# relays0.net
KiCad netlist of a schematic drawn in Altium Designer
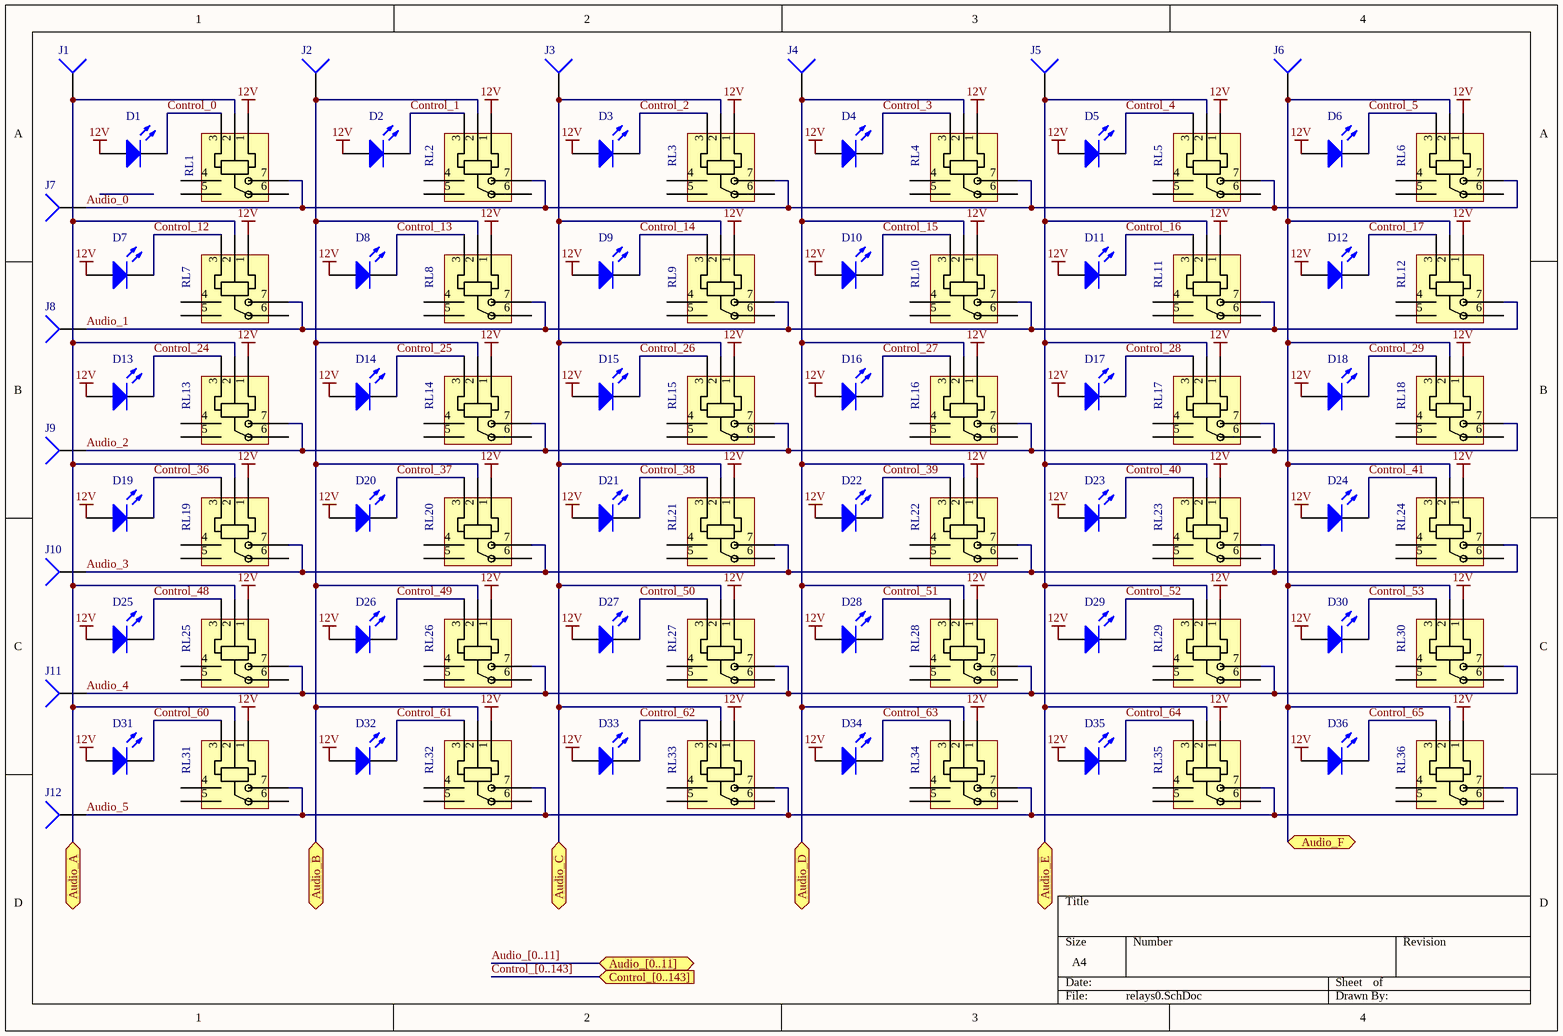
[diagram p0: relays0.SchDoc]

(export (version "E")
  (design (tool "Eeschema 10.0.6"))
  (components
    (comp (ref "D1")
      (value "LED0")
      (footprint "LED_round_5mm")
      (description "Typical INFRARED GaAs LED")
      (fields (field (name "PUBLISHER") "Altium Limited"))
      (libsource (lib "Miscellaneous Devices") (part "LED0"))
    )
    (comp (ref "D2")
      (value "LED0")
      (footprint "LED_round_5mm")
      (description "Typical INFRARED GaAs LED")
      (fields (field (name "PUBLISHER") "Altium Limited"))
      (libsource (lib "Miscellaneous Devices") (part "LED0"))
    )
    (comp (ref "D3")
      (value "LED0")
      (footprint "LED_round_5mm")
      (description "Typical INFRARED GaAs LED")
      (fields (field (name "PUBLISHER") "Altium Limited"))
      (libsource (lib "Miscellaneous Devices") (part "LED0"))
    )
    (comp (ref "D4")
      (value "LED0")
      (footprint "LED_round_5mm")
      (description "Typical INFRARED GaAs LED")
      (fields (field (name "PUBLISHER") "Altium Limited"))
      (libsource (lib "Miscellaneous Devices") (part "LED0"))
    )
    (comp (ref "D5")
      (value "LED0")
      (footprint "LED_round_5mm")
      (description "Typical INFRARED GaAs LED")
      (fields (field (name "PUBLISHER") "Altium Limited"))
      (libsource (lib "Miscellaneous Devices") (part "LED0"))
    )
    (comp (ref "D6")
      (value "LED0")
      (footprint "LED_round_5mm")
      (description "Typical INFRARED GaAs LED")
      (fields (field (name "PUBLISHER") "Altium Limited"))
      (libsource (lib "Miscellaneous Devices") (part "LED0"))
    )
    (comp (ref "D7")
      (value "LED0")
      (footprint "LED_round_5mm")
      (description "Typical INFRARED GaAs LED")
      (fields (field (name "PUBLISHER") "Altium Limited"))
      (libsource (lib "Miscellaneous Devices") (part "LED0"))
    )
    (comp (ref "D8")
      (value "LED0")
      (footprint "LED_round_5mm")
      (description "Typical INFRARED GaAs LED")
      (fields (field (name "PUBLISHER") "Altium Limited"))
      (libsource (lib "Miscellaneous Devices") (part "LED0"))
    )
    (comp (ref "D9")
      (value "LED0")
      (footprint "LED_round_5mm")
      (description "Typical INFRARED GaAs LED")
      (fields (field (name "PUBLISHER") "Altium Limited"))
      (libsource (lib "Miscellaneous Devices") (part "LED0"))
    )
    (comp (ref "D10")
      (value "LED0")
      (footprint "LED_round_5mm")
      (description "Typical INFRARED GaAs LED")
      (fields (field (name "PUBLISHER") "Altium Limited"))
      (libsource (lib "Miscellaneous Devices") (part "LED0"))
    )
    (comp (ref "D11")
      (value "LED0")
      (footprint "LED_round_5mm")
      (description "Typical INFRARED GaAs LED")
      (fields (field (name "PUBLISHER") "Altium Limited"))
      (libsource (lib "Miscellaneous Devices") (part "LED0"))
    )
    (comp (ref "D12")
      (value "LED0")
      (footprint "LED_round_5mm")
      (description "Typical INFRARED GaAs LED")
      (fields (field (name "PUBLISHER") "Altium Limited"))
      (libsource (lib "Miscellaneous Devices") (part "LED0"))
    )
    (comp (ref "D13")
      (value "LED0")
      (footprint "LED_round_5mm")
      (description "Typical INFRARED GaAs LED")
      (fields (field (name "PUBLISHER") "Altium Limited"))
      (libsource (lib "Miscellaneous Devices") (part "LED0"))
    )
    (comp (ref "D14")
      (value "LED0")
      (footprint "LED_round_5mm")
      (description "Typical INFRARED GaAs LED")
      (fields (field (name "PUBLISHER") "Altium Limited"))
      (libsource (lib "Miscellaneous Devices") (part "LED0"))
    )
    (comp (ref "D15")
      (value "LED0")
      (footprint "LED_round_5mm")
      (description "Typical INFRARED GaAs LED")
      (fields (field (name "PUBLISHER") "Altium Limited"))
      (libsource (lib "Miscellaneous Devices") (part "LED0"))
    )
    (comp (ref "D16")
      (value "LED0")
      (footprint "LED_round_5mm")
      (description "Typical INFRARED GaAs LED")
      (fields (field (name "PUBLISHER") "Altium Limited"))
      (libsource (lib "Miscellaneous Devices") (part "LED0"))
    )
    (comp (ref "D17")
      (value "LED0")
      (footprint "LED_round_5mm")
      (description "Typical INFRARED GaAs LED")
      (fields (field (name "PUBLISHER") "Altium Limited"))
      (libsource (lib "Miscellaneous Devices") (part "LED0"))
    )
    (comp (ref "D18")
      (value "LED0")
      (footprint "LED_round_5mm")
      (description "Typical INFRARED GaAs LED")
      (fields (field (name "PUBLISHER") "Altium Limited"))
      (libsource (lib "Miscellaneous Devices") (part "LED0"))
    )
    (comp (ref "D19")
      (value "LED0")
      (footprint "LED_round_5mm")
      (description "Typical INFRARED GaAs LED")
      (fields (field (name "PUBLISHER") "Altium Limited"))
      (libsource (lib "Miscellaneous Devices") (part "LED0"))
    )
    (comp (ref "D20")
      (value "LED0")
      (footprint "LED_round_5mm")
      (description "Typical INFRARED GaAs LED")
      (fields (field (name "PUBLISHER") "Altium Limited"))
      (libsource (lib "Miscellaneous Devices") (part "LED0"))
    )
    (comp (ref "D21")
      (value "LED0")
      (footprint "LED_round_5mm")
      (description "Typical INFRARED GaAs LED")
      (fields (field (name "PUBLISHER") "Altium Limited"))
      (libsource (lib "Miscellaneous Devices") (part "LED0"))
    )
    (comp (ref "D22")
      (value "LED0")
      (footprint "LED_round_5mm")
      (description "Typical INFRARED GaAs LED")
      (fields (field (name "PUBLISHER") "Altium Limited"))
      (libsource (lib "Miscellaneous Devices") (part "LED0"))
    )
    (comp (ref "D23")
      (value "LED0")
      (footprint "LED_round_5mm")
      (description "Typical INFRARED GaAs LED")
      (fields (field (name "PUBLISHER") "Altium Limited"))
      (libsource (lib "Miscellaneous Devices") (part "LED0"))
    )
    (comp (ref "D24")
      (value "LED0")
      (footprint "LED_round_5mm")
      (description "Typical INFRARED GaAs LED")
      (fields (field (name "PUBLISHER") "Altium Limited"))
      (libsource (lib "Miscellaneous Devices") (part "LED0"))
    )
    (comp (ref "D25")
      (value "LED0")
      (footprint "LED_round_5mm")
      (description "Typical INFRARED GaAs LED")
      (fields (field (name "PUBLISHER") "Altium Limited"))
      (libsource (lib "Miscellaneous Devices") (part "LED0"))
    )
    (comp (ref "D26")
      (value "LED0")
      (footprint "LED_round_5mm")
      (description "Typical INFRARED GaAs LED")
      (fields (field (name "PUBLISHER") "Altium Limited"))
      (libsource (lib "Miscellaneous Devices") (part "LED0"))
    )
    (comp (ref "D27")
      (value "LED0")
      (footprint "LED_round_5mm")
      (description "Typical INFRARED GaAs LED")
      (fields (field (name "PUBLISHER") "Altium Limited"))
      (libsource (lib "Miscellaneous Devices") (part "LED0"))
    )
    (comp (ref "D28")
      (value "LED0")
      (footprint "LED_round_5mm")
      (description "Typical INFRARED GaAs LED")
      (fields (field (name "PUBLISHER") "Altium Limited"))
      (libsource (lib "Miscellaneous Devices") (part "LED0"))
    )
    (comp (ref "D29")
      (value "LED0")
      (footprint "LED_round_5mm")
      (description "Typical INFRARED GaAs LED")
      (fields (field (name "PUBLISHER") "Altium Limited"))
      (libsource (lib "Miscellaneous Devices") (part "LED0"))
    )
    (comp (ref "D30")
      (value "LED0")
      (footprint "LED_round_5mm")
      (description "Typical INFRARED GaAs LED")
      (fields (field (name "PUBLISHER") "Altium Limited"))
      (libsource (lib "Miscellaneous Devices") (part "LED0"))
    )
    (comp (ref "D31")
      (value "LED0")
      (footprint "LED_round_5mm")
      (description "Typical INFRARED GaAs LED")
      (fields (field (name "PUBLISHER") "Altium Limited"))
      (libsource (lib "Miscellaneous Devices") (part "LED0"))
    )
    (comp (ref "D32")
      (value "LED0")
      (footprint "LED_round_5mm")
      (description "Typical INFRARED GaAs LED")
      (fields (field (name "PUBLISHER") "Altium Limited"))
      (libsource (lib "Miscellaneous Devices") (part "LED0"))
    )
    (comp (ref "D33")
      (value "LED0")
      (footprint "LED_round_5mm")
      (description "Typical INFRARED GaAs LED")
      (fields (field (name "PUBLISHER") "Altium Limited"))
      (libsource (lib "Miscellaneous Devices") (part "LED0"))
    )
    (comp (ref "D34")
      (value "LED0")
      (footprint "LED_round_5mm")
      (description "Typical INFRARED GaAs LED")
      (fields (field (name "PUBLISHER") "Altium Limited"))
      (libsource (lib "Miscellaneous Devices") (part "LED0"))
    )
    (comp (ref "D35")
      (value "LED0")
      (footprint "LED_round_5mm")
      (description "Typical INFRARED GaAs LED")
      (fields (field (name "PUBLISHER") "Altium Limited"))
      (libsource (lib "Miscellaneous Devices") (part "LED0"))
    )
    (comp (ref "D36")
      (value "LED0")
      (footprint "LED_round_5mm")
      (description "Typical INFRARED GaAs LED")
      (fields (field (name "PUBLISHER") "Altium Limited"))
      (libsource (lib "Miscellaneous Devices") (part "LED0"))
    )
    (comp (ref "J1")
      (value "Audio")
      (footprint "Conn_1_2x4")
      (description "Socket")
      (fields (field (name "PUBLISHER") "Altium Limited"))
      (libsource (lib "Miscellaneous Connectors") (part "Socket"))
    )
    (comp (ref "J2")
      (value "Audio")
      (footprint "Conn_1_2x4")
      (description "Socket")
      (fields (field (name "PUBLISHER") "Altium Limited"))
      (libsource (lib "Miscellaneous Connectors") (part "Socket"))
    )
    (comp (ref "J3")
      (value "Audio")
      (footprint "Conn_1_2x4")
      (description "Socket")
      (fields (field (name "PUBLISHER") "Altium Limited"))
      (libsource (lib "Miscellaneous Connectors") (part "Socket"))
    )
    (comp (ref "J4")
      (value "Audio")
      (footprint "Conn_1_2x4")
      (description "Socket")
      (fields (field (name "PUBLISHER") "Altium Limited"))
      (libsource (lib "Miscellaneous Connectors") (part "Socket"))
    )
    (comp (ref "J5")
      (value "Audio")
      (footprint "Conn_1_2x4")
      (description "Socket")
      (fields (field (name "PUBLISHER") "Altium Limited"))
      (libsource (lib "Miscellaneous Connectors") (part "Socket"))
    )
    (comp (ref "J6")
      (value "Audio")
      (footprint "Conn_1_2x4")
      (description "Socket")
      (fields (field (name "PUBLISHER") "Altium Limited"))
      (libsource (lib "Miscellaneous Connectors") (part "Socket"))
    )
    (comp (ref "J7")
      (value "Audio")
      (footprint "Conn_1_2x4")
      (description "Socket")
      (fields (field (name "PUBLISHER") "Altium Limited"))
      (libsource (lib "Miscellaneous Connectors") (part "Socket"))
    )
    (comp (ref "J8")
      (value "Audio")
      (footprint "Conn_1_2x4")
      (description "Socket")
      (fields (field (name "PUBLISHER") "Altium Limited"))
      (libsource (lib "Miscellaneous Connectors") (part "Socket"))
    )
    (comp (ref "J9")
      (value "Audio")
      (footprint "Conn_1_2x4")
      (description "Socket")
      (fields (field (name "PUBLISHER") "Altium Limited"))
      (libsource (lib "Miscellaneous Connectors") (part "Socket"))
    )
    (comp (ref "J10")
      (value "Audio")
      (footprint "Conn_1_2x4")
      (description "Socket")
      (fields (field (name "PUBLISHER") "Altium Limited"))
      (libsource (lib "Miscellaneous Connectors") (part "Socket"))
    )
    (comp (ref "J11")
      (value "Audio")
      (footprint "Conn_1_2x4")
      (description "Socket")
      (fields (field (name "PUBLISHER") "Altium Limited"))
      (libsource (lib "Miscellaneous Connectors") (part "Socket"))
    )
    (comp (ref "J12")
      (value "Audio")
      (footprint "Conn_1_2x4")
      (description "Socket")
      (fields (field (name "PUBLISHER") "Altium Limited"))
      (libsource (lib "Miscellaneous Connectors") (part "Socket"))
    )
    (comp (ref "RL1")
      (value "Relay")
      (footprint "Relay_FRA3")
      (description "Miniature power relay")
      (fields (field (name "PART NUMBER") "FRA3C-DC12"))
      (libsource (lib "tech-thing") (part "Relay_FRA3"))
    )
    (comp (ref "RL2")
      (value "Relay")
      (footprint "Relay_FRA3")
      (description "Miniature power relay")
      (fields (field (name "PART NUMBER") "FRA3C-DC12"))
      (libsource (lib "tech-thing") (part "Relay_FRA3"))
    )
    (comp (ref "RL3")
      (value "Relay")
      (footprint "Relay_FRA3")
      (description "Miniature power relay")
      (fields (field (name "PART NUMBER") "FRA3C-DC12"))
      (libsource (lib "tech-thing") (part "Relay_FRA3"))
    )
    (comp (ref "RL4")
      (value "Relay")
      (footprint "Relay_FRA3")
      (description "Miniature power relay")
      (fields (field (name "PART NUMBER") "FRA3C-DC12"))
      (libsource (lib "tech-thing") (part "Relay_FRA3"))
    )
    (comp (ref "RL5")
      (value "Relay")
      (footprint "Relay_FRA3")
      (description "Miniature power relay")
      (fields (field (name "PART NUMBER") "FRA3C-DC12"))
      (libsource (lib "tech-thing") (part "Relay_FRA3"))
    )
    (comp (ref "RL6")
      (value "Relay")
      (footprint "Relay_FRA3")
      (description "Miniature power relay")
      (fields (field (name "PART NUMBER") "FRA3C-DC12"))
      (libsource (lib "tech-thing") (part "Relay_FRA3"))
    )
    (comp (ref "RL7")
      (value "Relay")
      (footprint "Relay_FRA3")
      (description "Miniature power relay")
      (fields (field (name "PART NUMBER") "FRA3C-DC12"))
      (libsource (lib "tech-thing") (part "Relay_FRA3"))
    )
    (comp (ref "RL8")
      (value "Relay")
      (footprint "Relay_FRA3")
      (description "Miniature power relay")
      (fields (field (name "PART NUMBER") "FRA3C-DC12"))
      (libsource (lib "tech-thing") (part "Relay_FRA3"))
    )
    (comp (ref "RL9")
      (value "Relay")
      (footprint "Relay_FRA3")
      (description "Miniature power relay")
      (fields (field (name "PART NUMBER") "FRA3C-DC12"))
      (libsource (lib "tech-thing") (part "Relay_FRA3"))
    )
    (comp (ref "RL10")
      (value "Relay")
      (footprint "Relay_FRA3")
      (description "Miniature power relay")
      (fields (field (name "PART NUMBER") "FRA3C-DC12"))
      (libsource (lib "tech-thing") (part "Relay_FRA3"))
    )
    (comp (ref "RL11")
      (value "Relay")
      (footprint "Relay_FRA3")
      (description "Miniature power relay")
      (fields (field (name "PART NUMBER") "FRA3C-DC12"))
      (libsource (lib "tech-thing") (part "Relay_FRA3"))
    )
    (comp (ref "RL12")
      (value "Relay")
      (footprint "Relay_FRA3")
      (description "Miniature power relay")
      (fields (field (name "PART NUMBER") "FRA3C-DC12"))
      (libsource (lib "tech-thing") (part "Relay_FRA3"))
    )
    (comp (ref "RL13")
      (value "Relay")
      (footprint "Relay_FRA3")
      (description "Miniature power relay")
      (fields (field (name "PART NUMBER") "FRA3C-DC12"))
      (libsource (lib "tech-thing") (part "Relay_FRA3"))
    )
    (comp (ref "RL14")
      (value "Relay")
      (footprint "Relay_FRA3")
      (description "Miniature power relay")
      (fields (field (name "PART NUMBER") "FRA3C-DC12"))
      (libsource (lib "tech-thing") (part "Relay_FRA3"))
    )
    (comp (ref "RL15")
      (value "Relay")
      (footprint "Relay_FRA3")
      (description "Miniature power relay")
      (fields (field (name "PART NUMBER") "FRA3C-DC12"))
      (libsource (lib "tech-thing") (part "Relay_FRA3"))
    )
    (comp (ref "RL16")
      (value "Relay")
      (footprint "Relay_FRA3")
      (description "Miniature power relay")
      (fields (field (name "PART NUMBER") "FRA3C-DC12"))
      (libsource (lib "tech-thing") (part "Relay_FRA3"))
    )
    (comp (ref "RL17")
      (value "Relay")
      (footprint "Relay_FRA3")
      (description "Miniature power relay")
      (fields (field (name "PART NUMBER") "FRA3C-DC12"))
      (libsource (lib "tech-thing") (part "Relay_FRA3"))
    )
    (comp (ref "RL18")
      (value "Relay")
      (footprint "Relay_FRA3")
      (description "Miniature power relay")
      (fields (field (name "PART NUMBER") "FRA3C-DC12"))
      (libsource (lib "tech-thing") (part "Relay_FRA3"))
    )
    (comp (ref "RL19")
      (value "Relay")
      (footprint "Relay_FRA3")
      (description "Miniature power relay")
      (fields (field (name "PART NUMBER") "FRA3C-DC12"))
      (libsource (lib "tech-thing") (part "Relay_FRA3"))
    )
    (comp (ref "RL20")
      (value "Relay")
      (footprint "Relay_FRA3")
      (description "Miniature power relay")
      (fields (field (name "PART NUMBER") "FRA3C-DC12"))
      (libsource (lib "tech-thing") (part "Relay_FRA3"))
    )
    (comp (ref "RL21")
      (value "Relay")
      (footprint "Relay_FRA3")
      (description "Miniature power relay")
      (fields (field (name "PART NUMBER") "FRA3C-DC12"))
      (libsource (lib "tech-thing") (part "Relay_FRA3"))
    )
    (comp (ref "RL22")
      (value "Relay")
      (footprint "Relay_FRA3")
      (description "Miniature power relay")
      (fields (field (name "PART NUMBER") "FRA3C-DC12"))
      (libsource (lib "tech-thing") (part "Relay_FRA3"))
    )
    (comp (ref "RL23")
      (value "Relay")
      (footprint "Relay_FRA3")
      (description "Miniature power relay")
      (fields (field (name "PART NUMBER") "FRA3C-DC12"))
      (libsource (lib "tech-thing") (part "Relay_FRA3"))
    )
    (comp (ref "RL24")
      (value "Relay")
      (footprint "Relay_FRA3")
      (description "Miniature power relay")
      (fields (field (name "PART NUMBER") "FRA3C-DC12"))
      (libsource (lib "tech-thing") (part "Relay_FRA3"))
    )
    (comp (ref "RL25")
      (value "Relay")
      (footprint "Relay_FRA3")
      (description "Miniature power relay")
      (fields (field (name "PART NUMBER") "FRA3C-DC12"))
      (libsource (lib "tech-thing") (part "Relay_FRA3"))
    )
    (comp (ref "RL26")
      (value "Relay")
      (footprint "Relay_FRA3")
      (description "Miniature power relay")
      (fields (field (name "PART NUMBER") "FRA3C-DC12"))
      (libsource (lib "tech-thing") (part "Relay_FRA3"))
    )
    (comp (ref "RL27")
      (value "Relay")
      (footprint "Relay_FRA3")
      (description "Miniature power relay")
      (fields (field (name "PART NUMBER") "FRA3C-DC12"))
      (libsource (lib "tech-thing") (part "Relay_FRA3"))
    )
    (comp (ref "RL28")
      (value "Relay")
      (footprint "Relay_FRA3")
      (description "Miniature power relay")
      (fields (field (name "PART NUMBER") "FRA3C-DC12"))
      (libsource (lib "tech-thing") (part "Relay_FRA3"))
    )
    (comp (ref "RL29")
      (value "Relay")
      (footprint "Relay_FRA3")
      (description "Miniature power relay")
      (fields (field (name "PART NUMBER") "FRA3C-DC12"))
      (libsource (lib "tech-thing") (part "Relay_FRA3"))
    )
    (comp (ref "RL30")
      (value "Relay")
      (footprint "Relay_FRA3")
      (description "Miniature power relay")
      (fields (field (name "PART NUMBER") "FRA3C-DC12"))
      (libsource (lib "tech-thing") (part "Relay_FRA3"))
    )
    (comp (ref "RL31")
      (value "Relay")
      (footprint "Relay_FRA3")
      (description "Miniature power relay")
      (fields (field (name "PART NUMBER") "FRA3C-DC12"))
      (libsource (lib "tech-thing") (part "Relay_FRA3"))
    )
    (comp (ref "RL32")
      (value "Relay")
      (footprint "Relay_FRA3")
      (description "Miniature power relay")
      (fields (field (name "PART NUMBER") "FRA3C-DC12"))
      (libsource (lib "tech-thing") (part "Relay_FRA3"))
    )
    (comp (ref "RL33")
      (value "Relay")
      (footprint "Relay_FRA3")
      (description "Miniature power relay")
      (fields (field (name "PART NUMBER") "FRA3C-DC12"))
      (libsource (lib "tech-thing") (part "Relay_FRA3"))
    )
    (comp (ref "RL34")
      (value "Relay")
      (footprint "Relay_FRA3")
      (description "Miniature power relay")
      (fields (field (name "PART NUMBER") "FRA3C-DC12"))
      (libsource (lib "tech-thing") (part "Relay_FRA3"))
    )
    (comp (ref "RL35")
      (value "Relay")
      (footprint "Relay_FRA3")
      (description "Miniature power relay")
      (fields (field (name "PART NUMBER") "FRA3C-DC12"))
      (libsource (lib "tech-thing") (part "Relay_FRA3"))
    )
    (comp (ref "RL36")
      (value "Relay")
      (footprint "Relay_FRA3")
      (description "Miniature power relay")
      (fields (field (name "PART NUMBER") "FRA3C-DC12"))
      (libsource (lib "tech-thing") (part "Relay_FRA3"))
    )
  )
  (nets
    (net (code "115") (name "/Audio_0") (class "Default")
      (node (ref "J7") (pin "1") (pinfunction "1_1") (pintype "passive"))
      (node (ref "RL1") (pin "7") (pintype "passive"))
      (node (ref "RL2") (pin "7") (pintype "passive"))
      (node (ref "RL3") (pin "7") (pintype "passive"))
      (node (ref "RL4") (pin "7") (pintype "passive"))
      (node (ref "RL5") (pin "7") (pintype "passive"))
      (node (ref "RL6") (pin "7") (pintype "passive"))
    )
    (net (code "116") (name "/Audio_1") (class "Default")
      (node (ref "J8") (pin "1") (pinfunction "1_1") (pintype "passive"))
      (node (ref "RL10") (pin "7") (pintype "passive"))
      (node (ref "RL11") (pin "7") (pintype "passive"))
      (node (ref "RL12") (pin "7") (pintype "passive"))
      (node (ref "RL7") (pin "7") (pintype "passive"))
      (node (ref "RL8") (pin "7") (pintype "passive"))
      (node (ref "RL9") (pin "7") (pintype "passive"))
    )
    (net (code "117") (name "/Audio_2") (class "Default")
      (node (ref "J9") (pin "1") (pinfunction "1_1") (pintype "passive"))
      (node (ref "RL13") (pin "7") (pintype "passive"))
      (node (ref "RL14") (pin "7") (pintype "passive"))
      (node (ref "RL15") (pin "7") (pintype "passive"))
      (node (ref "RL16") (pin "7") (pintype "passive"))
      (node (ref "RL17") (pin "7") (pintype "passive"))
      (node (ref "RL18") (pin "7") (pintype "passive"))
    )
    (net (code "118") (name "/Audio_3") (class "Default")
      (node (ref "J10") (pin "1") (pinfunction "1_1") (pintype "passive"))
      (node (ref "RL19") (pin "7") (pintype "passive"))
      (node (ref "RL20") (pin "7") (pintype "passive"))
      (node (ref "RL21") (pin "7") (pintype "passive"))
      (node (ref "RL22") (pin "7") (pintype "passive"))
      (node (ref "RL23") (pin "7") (pintype "passive"))
      (node (ref "RL24") (pin "7") (pintype "passive"))
    )
    (net (code "119") (name "/Audio_4") (class "Default")
      (node (ref "J11") (pin "1") (pinfunction "1_1") (pintype "passive"))
      (node (ref "RL25") (pin "7") (pintype "passive"))
      (node (ref "RL26") (pin "7") (pintype "passive"))
      (node (ref "RL27") (pin "7") (pintype "passive"))
      (node (ref "RL28") (pin "7") (pintype "passive"))
      (node (ref "RL29") (pin "7") (pintype "passive"))
      (node (ref "RL30") (pin "7") (pintype "passive"))
    )
    (net (code "120") (name "/Audio_5") (class "Default")
      (node (ref "J12") (pin "1") (pinfunction "1_1") (pintype "passive"))
      (node (ref "RL31") (pin "7") (pintype "passive"))
      (node (ref "RL32") (pin "7") (pintype "passive"))
      (node (ref "RL33") (pin "7") (pintype "passive"))
      (node (ref "RL34") (pin "7") (pintype "passive"))
      (node (ref "RL35") (pin "7") (pintype "passive"))
      (node (ref "RL36") (pin "7") (pintype "passive"))
    )
    (net (code "121") (name "/Audio_A") (class "Default")
      (node (ref "J1") (pin "1") (pinfunction "1_1") (pintype "passive"))
      (node (ref "RL1") (pin "2") (pintype "passive"))
      (node (ref "RL13") (pin "2") (pintype "passive"))
      (node (ref "RL19") (pin "2") (pintype "passive"))
      (node (ref "RL25") (pin "2") (pintype "passive"))
      (node (ref "RL31") (pin "2") (pintype "passive"))
      (node (ref "RL7") (pin "2") (pintype "passive"))
    )
    (net (code "122") (name "/Audio_B") (class "Default")
      (node (ref "J2") (pin "1") (pinfunction "1_1") (pintype "passive"))
      (node (ref "RL14") (pin "2") (pintype "passive"))
      (node (ref "RL2") (pin "2") (pintype "passive"))
      (node (ref "RL20") (pin "2") (pintype "passive"))
      (node (ref "RL26") (pin "2") (pintype "passive"))
      (node (ref "RL32") (pin "2") (pintype "passive"))
      (node (ref "RL8") (pin "2") (pintype "passive"))
    )
    (net (code "123") (name "/Audio_C") (class "Default")
      (node (ref "J3") (pin "1") (pinfunction "1_1") (pintype "passive"))
      (node (ref "RL15") (pin "2") (pintype "passive"))
      (node (ref "RL21") (pin "2") (pintype "passive"))
      (node (ref "RL27") (pin "2") (pintype "passive"))
      (node (ref "RL3") (pin "2") (pintype "passive"))
      (node (ref "RL33") (pin "2") (pintype "passive"))
      (node (ref "RL9") (pin "2") (pintype "passive"))
    )
    (net (code "124") (name "/Audio_D") (class "Default")
      (node (ref "J4") (pin "1") (pinfunction "1_1") (pintype "passive"))
      (node (ref "RL10") (pin "2") (pintype "passive"))
      (node (ref "RL16") (pin "2") (pintype "passive"))
      (node (ref "RL22") (pin "2") (pintype "passive"))
      (node (ref "RL28") (pin "2") (pintype "passive"))
      (node (ref "RL34") (pin "2") (pintype "passive"))
      (node (ref "RL4") (pin "2") (pintype "passive"))
    )
    (net (code "125") (name "/Audio_E") (class "Default")
      (node (ref "J5") (pin "1") (pinfunction "1_1") (pintype "passive"))
      (node (ref "RL11") (pin "2") (pintype "passive"))
      (node (ref "RL17") (pin "2") (pintype "passive"))
      (node (ref "RL23") (pin "2") (pintype "passive"))
      (node (ref "RL29") (pin "2") (pintype "passive"))
      (node (ref "RL35") (pin "2") (pintype "passive"))
      (node (ref "RL5") (pin "2") (pintype "passive"))
    )
    (net (code "126") (name "/Audio_F") (class "Default")
      (node (ref "J6") (pin "1") (pinfunction "1_1") (pintype "passive"))
      (node (ref "RL12") (pin "2") (pintype "passive"))
      (node (ref "RL18") (pin "2") (pintype "passive"))
      (node (ref "RL24") (pin "2") (pintype "passive"))
      (node (ref "RL30") (pin "2") (pintype "passive"))
      (node (ref "RL36") (pin "2") (pintype "passive"))
      (node (ref "RL6") (pin "2") (pintype "passive"))
    )
    (net (code "128") (name "/Control_0") (class "Default")
      (node (ref "D1") (pin "2") (pinfunction "K_2") (pintype "passive"))
      (node (ref "RL1") (pin "3") (pintype "passive"))
    )
    (net (code "129") (name "/Control_1") (class "Default")
      (node (ref "D2") (pin "2") (pinfunction "K_2") (pintype "passive"))
      (node (ref "RL2") (pin "3") (pintype "passive"))
    )
    (net (code "130") (name "/Control_2") (class "Default")
      (node (ref "D3") (pin "2") (pinfunction "K_2") (pintype "passive"))
      (node (ref "RL3") (pin "3") (pintype "passive"))
    )
    (net (code "131") (name "/Control_3") (class "Default")
      (node (ref "D4") (pin "2") (pinfunction "K_2") (pintype "passive"))
      (node (ref "RL4") (pin "3") (pintype "passive"))
    )
    (net (code "132") (name "/Control_4") (class "Default")
      (node (ref "D5") (pin "2") (pinfunction "K_2") (pintype "passive"))
      (node (ref "RL5") (pin "3") (pintype "passive"))
    )
    (net (code "133") (name "/Control_5") (class "Default")
      (node (ref "D6") (pin "2") (pinfunction "K_2") (pintype "passive"))
      (node (ref "RL6") (pin "3") (pintype "passive"))
    )
    (net (code "134") (name "/Control_12") (class "Default")
      (node (ref "D7") (pin "2") (pinfunction "K_2") (pintype "passive"))
      (node (ref "RL7") (pin "3") (pintype "passive"))
    )
    (net (code "135") (name "/Control_13") (class "Default")
      (node (ref "D8") (pin "2") (pinfunction "K_2") (pintype "passive"))
      (node (ref "RL8") (pin "3") (pintype "passive"))
    )
    (net (code "136") (name "/Control_14") (class "Default")
      (node (ref "D9") (pin "2") (pinfunction "K_2") (pintype "passive"))
      (node (ref "RL9") (pin "3") (pintype "passive"))
    )
    (net (code "137") (name "/Control_15") (class "Default")
      (node (ref "D10") (pin "2") (pinfunction "K_2") (pintype "passive"))
      (node (ref "RL10") (pin "3") (pintype "passive"))
    )
    (net (code "138") (name "/Control_16") (class "Default")
      (node (ref "D11") (pin "2") (pinfunction "K_2") (pintype "passive"))
      (node (ref "RL11") (pin "3") (pintype "passive"))
    )
    (net (code "139") (name "/Control_17") (class "Default")
      (node (ref "D12") (pin "2") (pinfunction "K_2") (pintype "passive"))
      (node (ref "RL12") (pin "3") (pintype "passive"))
    )
    (net (code "140") (name "/Control_24") (class "Default")
      (node (ref "D13") (pin "2") (pinfunction "K_2") (pintype "passive"))
      (node (ref "RL13") (pin "3") (pintype "passive"))
    )
    (net (code "141") (name "/Control_25") (class "Default")
      (node (ref "D14") (pin "2") (pinfunction "K_2") (pintype "passive"))
      (node (ref "RL14") (pin "3") (pintype "passive"))
    )
    (net (code "142") (name "/Control_26") (class "Default")
      (node (ref "D15") (pin "2") (pinfunction "K_2") (pintype "passive"))
      (node (ref "RL15") (pin "3") (pintype "passive"))
    )
    (net (code "143") (name "/Control_27") (class "Default")
      (node (ref "D16") (pin "2") (pinfunction "K_2") (pintype "passive"))
      (node (ref "RL16") (pin "3") (pintype "passive"))
    )
    (net (code "144") (name "/Control_28") (class "Default")
      (node (ref "D17") (pin "2") (pinfunction "K_2") (pintype "passive"))
      (node (ref "RL17") (pin "3") (pintype "passive"))
    )
    (net (code "145") (name "/Control_29") (class "Default")
      (node (ref "D18") (pin "2") (pinfunction "K_2") (pintype "passive"))
      (node (ref "RL18") (pin "3") (pintype "passive"))
    )
    (net (code "146") (name "/Control_36") (class "Default")
      (node (ref "D19") (pin "2") (pinfunction "K_2") (pintype "passive"))
      (node (ref "RL19") (pin "3") (pintype "passive"))
    )
    (net (code "147") (name "/Control_37") (class "Default")
      (node (ref "D20") (pin "2") (pinfunction "K_2") (pintype "passive"))
      (node (ref "RL20") (pin "3") (pintype "passive"))
    )
    (net (code "148") (name "/Control_38") (class "Default")
      (node (ref "D21") (pin "2") (pinfunction "K_2") (pintype "passive"))
      (node (ref "RL21") (pin "3") (pintype "passive"))
    )
    (net (code "149") (name "/Control_39") (class "Default")
      (node (ref "D22") (pin "2") (pinfunction "K_2") (pintype "passive"))
      (node (ref "RL22") (pin "3") (pintype "passive"))
    )
    (net (code "150") (name "/Control_40") (class "Default")
      (node (ref "D23") (pin "2") (pinfunction "K_2") (pintype "passive"))
      (node (ref "RL23") (pin "3") (pintype "passive"))
    )
    (net (code "151") (name "/Control_41") (class "Default")
      (node (ref "D24") (pin "2") (pinfunction "K_2") (pintype "passive"))
      (node (ref "RL24") (pin "3") (pintype "passive"))
    )
    (net (code "152") (name "/Control_48") (class "Default")
      (node (ref "D25") (pin "2") (pinfunction "K_2") (pintype "passive"))
      (node (ref "RL25") (pin "3") (pintype "passive"))
    )
    (net (code "153") (name "/Control_49") (class "Default")
      (node (ref "D26") (pin "2") (pinfunction "K_2") (pintype "passive"))
      (node (ref "RL26") (pin "3") (pintype "passive"))
    )
    (net (code "154") (name "/Control_50") (class "Default")
      (node (ref "D27") (pin "2") (pinfunction "K_2") (pintype "passive"))
      (node (ref "RL27") (pin "3") (pintype "passive"))
    )
    (net (code "155") (name "/Control_51") (class "Default")
      (node (ref "D28") (pin "2") (pinfunction "K_2") (pintype "passive"))
      (node (ref "RL28") (pin "3") (pintype "passive"))
    )
    (net (code "156") (name "/Control_52") (class "Default")
      (node (ref "D29") (pin "2") (pinfunction "K_2") (pintype "passive"))
      (node (ref "RL29") (pin "3") (pintype "passive"))
    )
    (net (code "157") (name "/Control_53") (class "Default")
      (node (ref "D30") (pin "2") (pinfunction "K_2") (pintype "passive"))
      (node (ref "RL30") (pin "3") (pintype "passive"))
    )
    (net (code "158") (name "/Control_60") (class "Default")
      (node (ref "D31") (pin "2") (pinfunction "K_2") (pintype "passive"))
      (node (ref "RL31") (pin "3") (pintype "passive"))
    )
    (net (code "159") (name "/Control_61") (class "Default")
      (node (ref "D32") (pin "2") (pinfunction "K_2") (pintype "passive"))
      (node (ref "RL32") (pin "3") (pintype "passive"))
    )
    (net (code "160") (name "/Control_62") (class "Default")
      (node (ref "D33") (pin "2") (pinfunction "K_2") (pintype "passive"))
      (node (ref "RL33") (pin "3") (pintype "passive"))
    )
    (net (code "161") (name "/Control_63") (class "Default")
      (node (ref "D34") (pin "2") (pinfunction "K_2") (pintype "passive"))
      (node (ref "RL34") (pin "3") (pintype "passive"))
    )
    (net (code "162") (name "/Control_64") (class "Default")
      (node (ref "D35") (pin "2") (pinfunction "K_2") (pintype "passive"))
      (node (ref "RL35") (pin "3") (pintype "passive"))
    )
    (net (code "163") (name "/Control_65") (class "Default")
      (node (ref "D36") (pin "2") (pinfunction "K_2") (pintype "passive"))
      (node (ref "RL36") (pin "3") (pintype "passive"))
    )
    (net (code "165") (name "12V") (class "Default")
      (node (ref "D1") (pin "1") (pinfunction "A_1") (pintype "passive"))
      (node (ref "D10") (pin "1") (pinfunction "A_1") (pintype "passive"))
      (node (ref "D11") (pin "1") (pinfunction "A_1") (pintype "passive"))
      (node (ref "D12") (pin "1") (pinfunction "A_1") (pintype "passive"))
      (node (ref "D13") (pin "1") (pinfunction "A_1") (pintype "passive"))
      (node (ref "D14") (pin "1") (pinfunction "A_1") (pintype "passive"))
      (node (ref "D15") (pin "1") (pinfunction "A_1") (pintype "passive"))
      (node (ref "D16") (pin "1") (pinfunction "A_1") (pintype "passive"))
      (node (ref "D17") (pin "1") (pinfunction "A_1") (pintype "passive"))
      (node (ref "D18") (pin "1") (pinfunction "A_1") (pintype "passive"))
      (node (ref "D19") (pin "1") (pinfunction "A_1") (pintype "passive"))
      (node (ref "D2") (pin "1") (pinfunction "A_1") (pintype "passive"))
      (node (ref "D20") (pin "1") (pinfunction "A_1") (pintype "passive"))
      (node (ref "D21") (pin "1") (pinfunction "A_1") (pintype "passive"))
      (node (ref "D22") (pin "1") (pinfunction "A_1") (pintype "passive"))
      (node (ref "D23") (pin "1") (pinfunction "A_1") (pintype "passive"))
      (node (ref "D24") (pin "1") (pinfunction "A_1") (pintype "passive"))
      (node (ref "D25") (pin "1") (pinfunction "A_1") (pintype "passive"))
      (node (ref "D26") (pin "1") (pinfunction "A_1") (pintype "passive"))
      (node (ref "D27") (pin "1") (pinfunction "A_1") (pintype "passive"))
      (node (ref "D28") (pin "1") (pinfunction "A_1") (pintype "passive"))
      (node (ref "D29") (pin "1") (pinfunction "A_1") (pintype "passive"))
      (node (ref "D3") (pin "1") (pinfunction "A_1") (pintype "passive"))
      (node (ref "D30") (pin "1") (pinfunction "A_1") (pintype "passive"))
      (node (ref "D31") (pin "1") (pinfunction "A_1") (pintype "passive"))
      (node (ref "D32") (pin "1") (pinfunction "A_1") (pintype "passive"))
      (node (ref "D33") (pin "1") (pinfunction "A_1") (pintype "passive"))
      (node (ref "D34") (pin "1") (pinfunction "A_1") (pintype "passive"))
      (node (ref "D35") (pin "1") (pinfunction "A_1") (pintype "passive"))
      (node (ref "D36") (pin "1") (pinfunction "A_1") (pintype "passive"))
      (node (ref "D4") (pin "1") (pinfunction "A_1") (pintype "passive"))
      (node (ref "D5") (pin "1") (pinfunction "A_1") (pintype "passive"))
      (node (ref "D6") (pin "1") (pinfunction "A_1") (pintype "passive"))
      (node (ref "D7") (pin "1") (pinfunction "A_1") (pintype "passive"))
      (node (ref "D8") (pin "1") (pinfunction "A_1") (pintype "passive"))
      (node (ref "D9") (pin "1") (pinfunction "A_1") (pintype "passive"))
      (node (ref "RL1") (pin "1") (pintype "passive"))
      (node (ref "RL10") (pin "1") (pintype "passive"))
      (node (ref "RL11") (pin "1") (pintype "passive"))
      (node (ref "RL12") (pin "1") (pintype "passive"))
      (node (ref "RL13") (pin "1") (pintype "passive"))
      (node (ref "RL14") (pin "1") (pintype "passive"))
      (node (ref "RL15") (pin "1") (pintype "passive"))
      (node (ref "RL16") (pin "1") (pintype "passive"))
      (node (ref "RL17") (pin "1") (pintype "passive"))
      (node (ref "RL18") (pin "1") (pintype "passive"))
      (node (ref "RL19") (pin "1") (pintype "passive"))
      (node (ref "RL2") (pin "1") (pintype "passive"))
      (node (ref "RL20") (pin "1") (pintype "passive"))
      (node (ref "RL21") (pin "1") (pintype "passive"))
      (node (ref "RL22") (pin "1") (pintype "passive"))
      (node (ref "RL23") (pin "1") (pintype "passive"))
      (node (ref "RL24") (pin "1") (pintype "passive"))
      (node (ref "RL25") (pin "1") (pintype "passive"))
      (node (ref "RL26") (pin "1") (pintype "passive"))
      (node (ref "RL27") (pin "1") (pintype "passive"))
      (node (ref "RL28") (pin "1") (pintype "passive"))
      (node (ref "RL29") (pin "1") (pintype "passive"))
      (node (ref "RL3") (pin "1") (pintype "passive"))
      (node (ref "RL30") (pin "1") (pintype "passive"))
      (node (ref "RL31") (pin "1") (pintype "passive"))
      (node (ref "RL32") (pin "1") (pintype "passive"))
      (node (ref "RL33") (pin "1") (pintype "passive"))
      (node (ref "RL34") (pin "1") (pintype "passive"))
      (node (ref "RL35") (pin "1") (pintype "passive"))
      (node (ref "RL36") (pin "1") (pintype "passive"))
      (node (ref "RL4") (pin "1") (pintype "passive"))
      (node (ref "RL5") (pin "1") (pintype "passive"))
      (node (ref "RL6") (pin "1") (pintype "passive"))
      (node (ref "RL7") (pin "1") (pintype "passive"))
      (node (ref "RL8") (pin "1") (pintype "passive"))
      (node (ref "RL9") (pin "1") (pintype "passive"))
    )
    (net (code "166") (name "unconnected-(RL1-Pad4)") (class "Default")
      (node (ref "RL1") (pin "4") (pintype "passive"))
    )
    (net (code "167") (name "unconnected-(RL1-Pad5)") (class "Default")
      (node (ref "RL1") (pin "5") (pintype "passive"))
    )
    (net (code "168") (name "unconnected-(RL1-Pad6)") (class "Default")
      (node (ref "RL1") (pin "6") (pintype "passive"))
    )
    (net (code "169") (name "unconnected-(RL2-Pad4)") (class "Default")
      (node (ref "RL2") (pin "4") (pintype "passive"))
    )
    (net (code "170") (name "unconnected-(RL2-Pad5)") (class "Default")
      (node (ref "RL2") (pin "5") (pintype "passive"))
    )
    (net (code "171") (name "unconnected-(RL2-Pad6)") (class "Default")
      (node (ref "RL2") (pin "6") (pintype "passive"))
    )
    (net (code "172") (name "unconnected-(RL3-Pad4)") (class "Default")
      (node (ref "RL3") (pin "4") (pintype "passive"))
    )
    (net (code "173") (name "unconnected-(RL3-Pad5)") (class "Default")
      (node (ref "RL3") (pin "5") (pintype "passive"))
    )
    (net (code "174") (name "unconnected-(RL3-Pad6)") (class "Default")
      (node (ref "RL3") (pin "6") (pintype "passive"))
    )
    (net (code "175") (name "unconnected-(RL4-Pad4)") (class "Default")
      (node (ref "RL4") (pin "4") (pintype "passive"))
    )
    (net (code "176") (name "unconnected-(RL4-Pad5)") (class "Default")
      (node (ref "RL4") (pin "5") (pintype "passive"))
    )
    (net (code "177") (name "unconnected-(RL4-Pad6)") (class "Default")
      (node (ref "RL4") (pin "6") (pintype "passive"))
    )
    (net (code "178") (name "unconnected-(RL5-Pad4)") (class "Default")
      (node (ref "RL5") (pin "4") (pintype "passive"))
    )
    (net (code "179") (name "unconnected-(RL5-Pad5)") (class "Default")
      (node (ref "RL5") (pin "5") (pintype "passive"))
    )
    (net (code "180") (name "unconnected-(RL5-Pad6)") (class "Default")
      (node (ref "RL5") (pin "6") (pintype "passive"))
    )
    (net (code "181") (name "unconnected-(RL6-Pad4)") (class "Default")
      (node (ref "RL6") (pin "4") (pintype "passive"))
    )
    (net (code "182") (name "unconnected-(RL6-Pad5)") (class "Default")
      (node (ref "RL6") (pin "5") (pintype "passive"))
    )
    (net (code "183") (name "unconnected-(RL6-Pad6)") (class "Default")
      (node (ref "RL6") (pin "6") (pintype "passive"))
    )
    (net (code "184") (name "unconnected-(RL7-Pad4)") (class "Default")
      (node (ref "RL7") (pin "4") (pintype "passive"))
    )
    (net (code "185") (name "unconnected-(RL7-Pad5)") (class "Default")
      (node (ref "RL7") (pin "5") (pintype "passive"))
    )
    (net (code "186") (name "unconnected-(RL7-Pad6)") (class "Default")
      (node (ref "RL7") (pin "6") (pintype "passive"))
    )
    (net (code "187") (name "unconnected-(RL8-Pad4)") (class "Default")
      (node (ref "RL8") (pin "4") (pintype "passive"))
    )
    (net (code "188") (name "unconnected-(RL8-Pad5)") (class "Default")
      (node (ref "RL8") (pin "5") (pintype "passive"))
    )
    (net (code "189") (name "unconnected-(RL8-Pad6)") (class "Default")
      (node (ref "RL8") (pin "6") (pintype "passive"))
    )
    (net (code "190") (name "unconnected-(RL9-Pad4)") (class "Default")
      (node (ref "RL9") (pin "4") (pintype "passive"))
    )
    (net (code "191") (name "unconnected-(RL9-Pad5)") (class "Default")
      (node (ref "RL9") (pin "5") (pintype "passive"))
    )
    (net (code "192") (name "unconnected-(RL9-Pad6)") (class "Default")
      (node (ref "RL9") (pin "6") (pintype "passive"))
    )
    (net (code "193") (name "unconnected-(RL10-Pad4)") (class "Default")
      (node (ref "RL10") (pin "4") (pintype "passive"))
    )
    (net (code "194") (name "unconnected-(RL10-Pad5)") (class "Default")
      (node (ref "RL10") (pin "5") (pintype "passive"))
    )
    (net (code "195") (name "unconnected-(RL10-Pad6)") (class "Default")
      (node (ref "RL10") (pin "6") (pintype "passive"))
    )
    (net (code "196") (name "unconnected-(RL11-Pad4)") (class "Default")
      (node (ref "RL11") (pin "4") (pintype "passive"))
    )
    (net (code "197") (name "unconnected-(RL11-Pad5)") (class "Default")
      (node (ref "RL11") (pin "5") (pintype "passive"))
    )
    (net (code "198") (name "unconnected-(RL11-Pad6)") (class "Default")
      (node (ref "RL11") (pin "6") (pintype "passive"))
    )
    (net (code "199") (name "unconnected-(RL12-Pad4)") (class "Default")
      (node (ref "RL12") (pin "4") (pintype "passive"))
    )
    (net (code "200") (name "unconnected-(RL12-Pad5)") (class "Default")
      (node (ref "RL12") (pin "5") (pintype "passive"))
    )
    (net (code "201") (name "unconnected-(RL12-Pad6)") (class "Default")
      (node (ref "RL12") (pin "6") (pintype "passive"))
    )
    (net (code "202") (name "unconnected-(RL13-Pad4)") (class "Default")
      (node (ref "RL13") (pin "4") (pintype "passive"))
    )
    (net (code "203") (name "unconnected-(RL13-Pad5)") (class "Default")
      (node (ref "RL13") (pin "5") (pintype "passive"))
    )
    (net (code "204") (name "unconnected-(RL13-Pad6)") (class "Default")
      (node (ref "RL13") (pin "6") (pintype "passive"))
    )
    (net (code "205") (name "unconnected-(RL14-Pad4)") (class "Default")
      (node (ref "RL14") (pin "4") (pintype "passive"))
    )
    (net (code "206") (name "unconnected-(RL14-Pad5)") (class "Default")
      (node (ref "RL14") (pin "5") (pintype "passive"))
    )
    (net (code "207") (name "unconnected-(RL14-Pad6)") (class "Default")
      (node (ref "RL14") (pin "6") (pintype "passive"))
    )
    (net (code "208") (name "unconnected-(RL15-Pad4)") (class "Default")
      (node (ref "RL15") (pin "4") (pintype "passive"))
    )
    (net (code "209") (name "unconnected-(RL15-Pad5)") (class "Default")
      (node (ref "RL15") (pin "5") (pintype "passive"))
    )
    (net (code "210") (name "unconnected-(RL15-Pad6)") (class "Default")
      (node (ref "RL15") (pin "6") (pintype "passive"))
    )
    (net (code "211") (name "unconnected-(RL16-Pad4)") (class "Default")
      (node (ref "RL16") (pin "4") (pintype "passive"))
    )
    (net (code "212") (name "unconnected-(RL16-Pad5)") (class "Default")
      (node (ref "RL16") (pin "5") (pintype "passive"))
    )
    (net (code "213") (name "unconnected-(RL16-Pad6)") (class "Default")
      (node (ref "RL16") (pin "6") (pintype "passive"))
    )
    (net (code "214") (name "unconnected-(RL17-Pad4)") (class "Default")
      (node (ref "RL17") (pin "4") (pintype "passive"))
    )
    (net (code "215") (name "unconnected-(RL17-Pad5)") (class "Default")
      (node (ref "RL17") (pin "5") (pintype "passive"))
    )
    (net (code "216") (name "unconnected-(RL17-Pad6)") (class "Default")
      (node (ref "RL17") (pin "6") (pintype "passive"))
    )
    (net (code "217") (name "unconnected-(RL18-Pad4)") (class "Default")
      (node (ref "RL18") (pin "4") (pintype "passive"))
    )
    (net (code "218") (name "unconnected-(RL18-Pad5)") (class "Default")
      (node (ref "RL18") (pin "5") (pintype "passive"))
    )
    (net (code "219") (name "unconnected-(RL18-Pad6)") (class "Default")
      (node (ref "RL18") (pin "6") (pintype "passive"))
    )
    (net (code "220") (name "unconnected-(RL19-Pad4)") (class "Default")
      (node (ref "RL19") (pin "4") (pintype "passive"))
    )
    (net (code "221") (name "unconnected-(RL19-Pad5)") (class "Default")
      (node (ref "RL19") (pin "5") (pintype "passive"))
    )
    (net (code "222") (name "unconnected-(RL19-Pad6)") (class "Default")
      (node (ref "RL19") (pin "6") (pintype "passive"))
    )
    (net (code "223") (name "unconnected-(RL20-Pad4)") (class "Default")
      (node (ref "RL20") (pin "4") (pintype "passive"))
    )
    (net (code "224") (name "unconnected-(RL20-Pad5)") (class "Default")
      (node (ref "RL20") (pin "5") (pintype "passive"))
    )
    (net (code "225") (name "unconnected-(RL20-Pad6)") (class "Default")
      (node (ref "RL20") (pin "6") (pintype "passive"))
    )
    (net (code "226") (name "unconnected-(RL21-Pad4)") (class "Default")
      (node (ref "RL21") (pin "4") (pintype "passive"))
    )
    (net (code "227") (name "unconnected-(RL21-Pad5)") (class "Default")
      (node (ref "RL21") (pin "5") (pintype "passive"))
    )
    (net (code "228") (name "unconnected-(RL21-Pad6)") (class "Default")
      (node (ref "RL21") (pin "6") (pintype "passive"))
    )
    (net (code "229") (name "unconnected-(RL22-Pad4)") (class "Default")
      (node (ref "RL22") (pin "4") (pintype "passive"))
    )
    (net (code "230") (name "unconnected-(RL22-Pad5)") (class "Default")
      (node (ref "RL22") (pin "5") (pintype "passive"))
    )
    (net (code "231") (name "unconnected-(RL22-Pad6)") (class "Default")
      (node (ref "RL22") (pin "6") (pintype "passive"))
    )
    (net (code "232") (name "unconnected-(RL23-Pad4)") (class "Default")
      (node (ref "RL23") (pin "4") (pintype "passive"))
    )
    (net (code "233") (name "unconnected-(RL23-Pad5)") (class "Default")
      (node (ref "RL23") (pin "5") (pintype "passive"))
    )
    (net (code "234") (name "unconnected-(RL23-Pad6)") (class "Default")
      (node (ref "RL23") (pin "6") (pintype "passive"))
    )
    (net (code "235") (name "unconnected-(RL24-Pad4)") (class "Default")
      (node (ref "RL24") (pin "4") (pintype "passive"))
    )
    (net (code "236") (name "unconnected-(RL24-Pad5)") (class "Default")
      (node (ref "RL24") (pin "5") (pintype "passive"))
    )
    (net (code "237") (name "unconnected-(RL24-Pad6)") (class "Default")
      (node (ref "RL24") (pin "6") (pintype "passive"))
    )
    (net (code "238") (name "unconnected-(RL25-Pad4)") (class "Default")
      (node (ref "RL25") (pin "4") (pintype "passive"))
    )
    (net (code "239") (name "unconnected-(RL25-Pad5)") (class "Default")
      (node (ref "RL25") (pin "5") (pintype "passive"))
    )
    (net (code "240") (name "unconnected-(RL25-Pad6)") (class "Default")
      (node (ref "RL25") (pin "6") (pintype "passive"))
    )
    (net (code "241") (name "unconnected-(RL26-Pad4)") (class "Default")
      (node (ref "RL26") (pin "4") (pintype "passive"))
    )
    (net (code "242") (name "unconnected-(RL26-Pad5)") (class "Default")
      (node (ref "RL26") (pin "5") (pintype "passive"))
    )
    (net (code "243") (name "unconnected-(RL26-Pad6)") (class "Default")
      (node (ref "RL26") (pin "6") (pintype "passive"))
    )
    (net (code "244") (name "unconnected-(RL27-Pad4)") (class "Default")
      (node (ref "RL27") (pin "4") (pintype "passive"))
    )
    (net (code "245") (name "unconnected-(RL27-Pad5)") (class "Default")
      (node (ref "RL27") (pin "5") (pintype "passive"))
    )
    (net (code "246") (name "unconnected-(RL27-Pad6)") (class "Default")
      (node (ref "RL27") (pin "6") (pintype "passive"))
    )
    (net (code "247") (name "unconnected-(RL28-Pad4)") (class "Default")
      (node (ref "RL28") (pin "4") (pintype "passive"))
    )
    (net (code "248") (name "unconnected-(RL28-Pad5)") (class "Default")
      (node (ref "RL28") (pin "5") (pintype "passive"))
    )
    (net (code "249") (name "unconnected-(RL28-Pad6)") (class "Default")
      (node (ref "RL28") (pin "6") (pintype "passive"))
    )
    (net (code "250") (name "unconnected-(RL29-Pad4)") (class "Default")
      (node (ref "RL29") (pin "4") (pintype "passive"))
    )
    (net (code "251") (name "unconnected-(RL29-Pad5)") (class "Default")
      (node (ref "RL29") (pin "5") (pintype "passive"))
    )
    (net (code "252") (name "unconnected-(RL29-Pad6)") (class "Default")
      (node (ref "RL29") (pin "6") (pintype "passive"))
    )
    (net (code "253") (name "unconnected-(RL30-Pad4)") (class "Default")
      (node (ref "RL30") (pin "4") (pintype "passive"))
    )
    (net (code "254") (name "unconnected-(RL30-Pad5)") (class "Default")
      (node (ref "RL30") (pin "5") (pintype "passive"))
    )
    (net (code "255") (name "unconnected-(RL30-Pad6)") (class "Default")
      (node (ref "RL30") (pin "6") (pintype "passive"))
    )
    (net (code "256") (name "unconnected-(RL31-Pad4)") (class "Default")
      (node (ref "RL31") (pin "4") (pintype "passive"))
    )
    (net (code "257") (name "unconnected-(RL31-Pad5)") (class "Default")
      (node (ref "RL31") (pin "5") (pintype "passive"))
    )
    (net (code "258") (name "unconnected-(RL31-Pad6)") (class "Default")
      (node (ref "RL31") (pin "6") (pintype "passive"))
    )
    (net (code "259") (name "unconnected-(RL32-Pad4)") (class "Default")
      (node (ref "RL32") (pin "4") (pintype "passive"))
    )
    (net (code "260") (name "unconnected-(RL32-Pad5)") (class "Default")
      (node (ref "RL32") (pin "5") (pintype "passive"))
    )
    (net (code "261") (name "unconnected-(RL32-Pad6)") (class "Default")
      (node (ref "RL32") (pin "6") (pintype "passive"))
    )
    (net (code "262") (name "unconnected-(RL33-Pad4)") (class "Default")
      (node (ref "RL33") (pin "4") (pintype "passive"))
    )
    (net (code "263") (name "unconnected-(RL33-Pad5)") (class "Default")
      (node (ref "RL33") (pin "5") (pintype "passive"))
    )
    (net (code "264") (name "unconnected-(RL33-Pad6)") (class "Default")
      (node (ref "RL33") (pin "6") (pintype "passive"))
    )
    (net (code "265") (name "unconnected-(RL34-Pad4)") (class "Default")
      (node (ref "RL34") (pin "4") (pintype "passive"))
    )
    (net (code "266") (name "unconnected-(RL34-Pad5)") (class "Default")
      (node (ref "RL34") (pin "5") (pintype "passive"))
    )
    (net (code "267") (name "unconnected-(RL34-Pad6)") (class "Default")
      (node (ref "RL34") (pin "6") (pintype "passive"))
    )
    (net (code "268") (name "unconnected-(RL35-Pad4)") (class "Default")
      (node (ref "RL35") (pin "4") (pintype "passive"))
    )
    (net (code "269") (name "unconnected-(RL35-Pad5)") (class "Default")
      (node (ref "RL35") (pin "5") (pintype "passive"))
    )
    (net (code "270") (name "unconnected-(RL35-Pad6)") (class "Default")
      (node (ref "RL35") (pin "6") (pintype "passive"))
    )
    (net (code "271") (name "unconnected-(RL36-Pad4)") (class "Default")
      (node (ref "RL36") (pin "4") (pintype "passive"))
    )
    (net (code "272") (name "unconnected-(RL36-Pad5)") (class "Default")
      (node (ref "RL36") (pin "5") (pintype "passive"))
    )
    (net (code "273") (name "unconnected-(RL36-Pad6)") (class "Default")
      (node (ref "RL36") (pin "6") (pintype "passive"))
    )
  )
)
